# 6-line-matrix.net
KiCad netlist of a schematic drawn in EAGLE
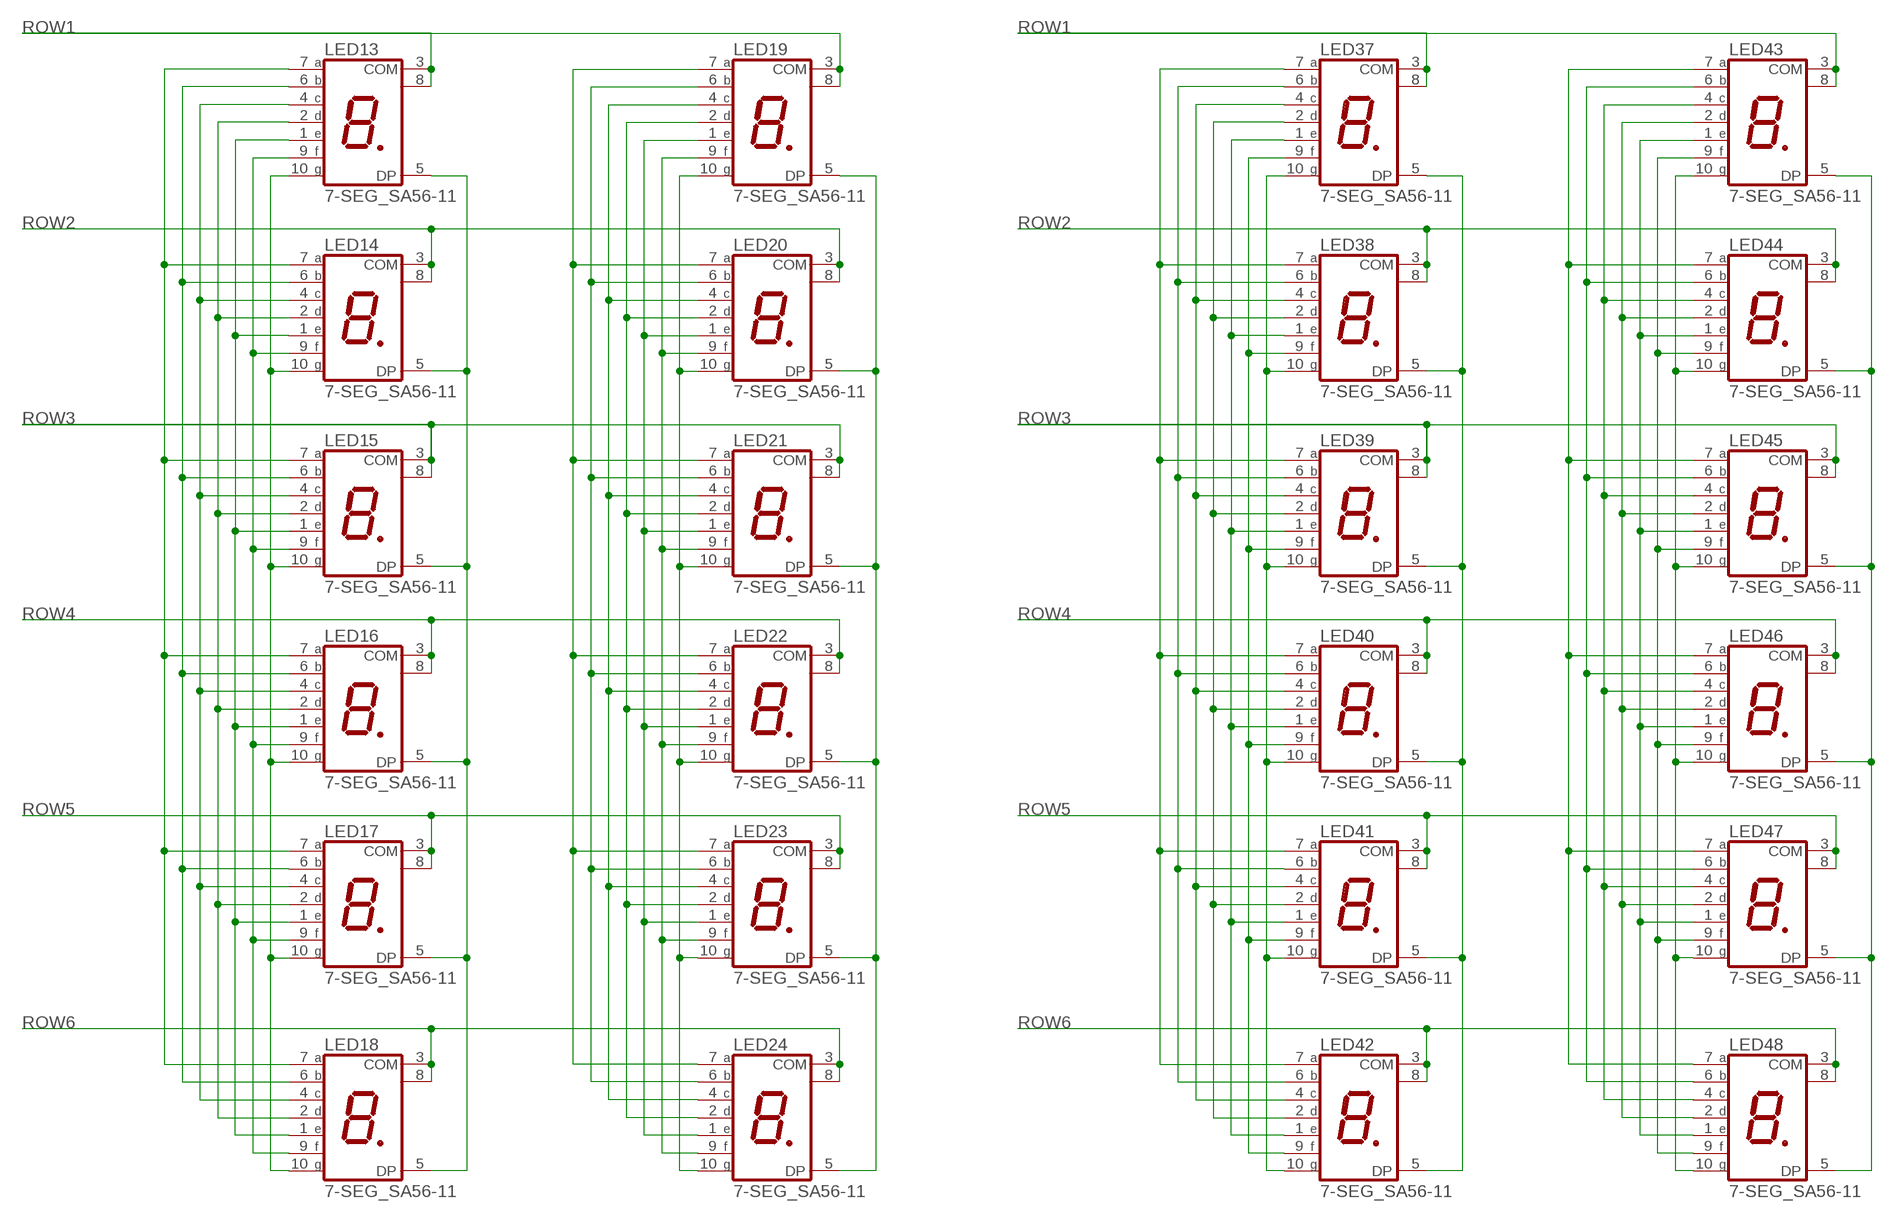
[diagram p0: schematic, sheet 1, part 1 of 2]
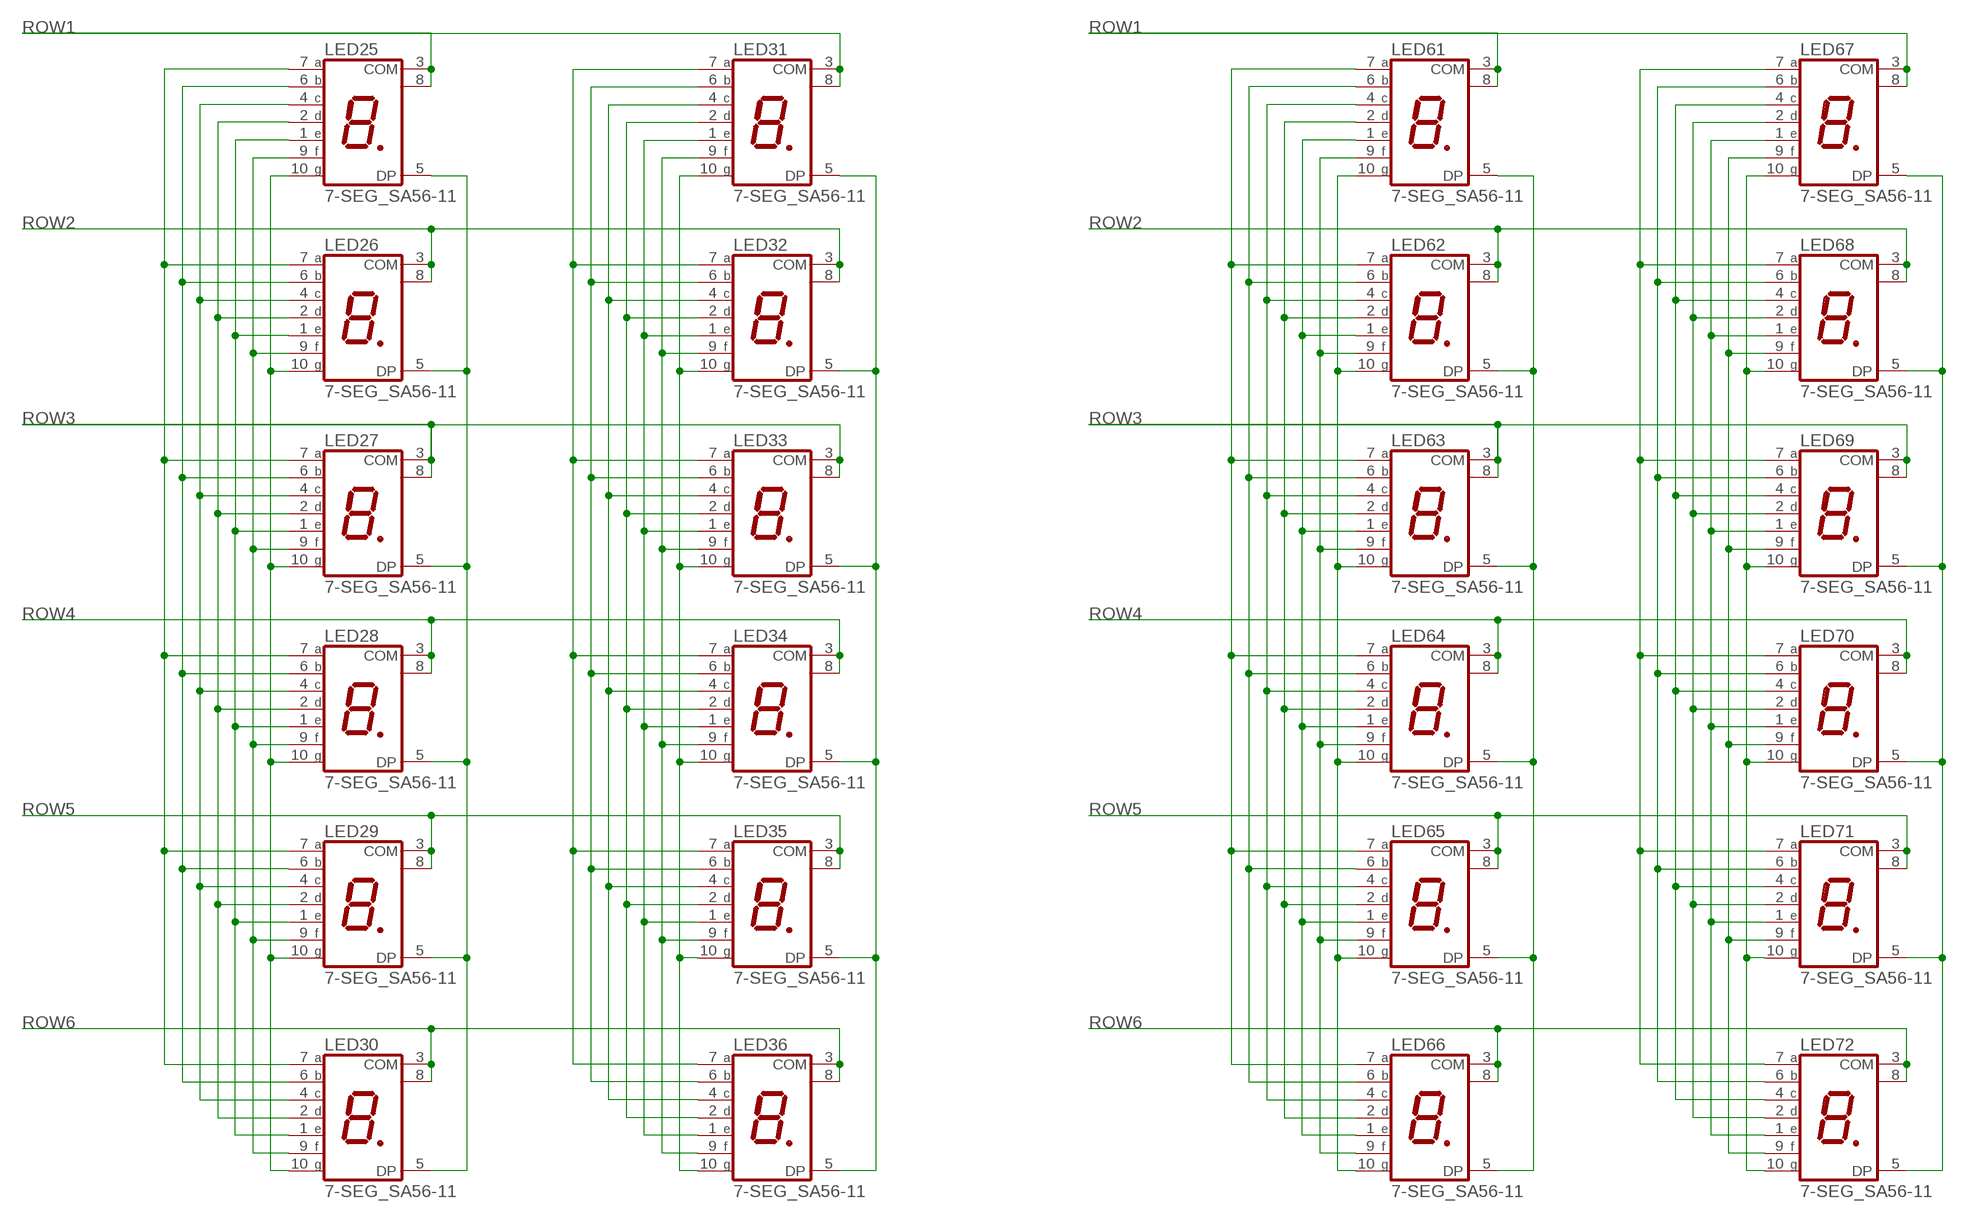
[diagram p1: schematic, sheet 1, part 2 of 2]

(export (version "E")
  (design (tool "Eeschema 10.0.6"))
  (components
    (comp (ref "LED13")
      (value "7-SEG_SA56-11")
      (footprint "eagle-import:SA56-11")
      (libsource (lib "eagle-import") (part "7-SEG_SA56-11"))
    )
    (comp (ref "LED14")
      (value "7-SEG_SA56-11")
      (footprint "eagle-import:SA56-11")
      (libsource (lib "eagle-import") (part "7-SEG_SA56-11"))
    )
    (comp (ref "LED15")
      (value "7-SEG_SA56-11")
      (footprint "eagle-import:SA56-11")
      (libsource (lib "eagle-import") (part "7-SEG_SA56-11"))
    )
    (comp (ref "LED16")
      (value "7-SEG_SA56-11")
      (footprint "eagle-import:SA56-11")
      (libsource (lib "eagle-import") (part "7-SEG_SA56-11"))
    )
    (comp (ref "LED17")
      (value "7-SEG_SA56-11")
      (footprint "eagle-import:SA56-11")
      (libsource (lib "eagle-import") (part "7-SEG_SA56-11"))
    )
    (comp (ref "LED18")
      (value "7-SEG_SA56-11")
      (footprint "eagle-import:SA56-11")
      (libsource (lib "eagle-import") (part "7-SEG_SA56-11"))
    )
    (comp (ref "LED19")
      (value "7-SEG_SA56-11")
      (footprint "eagle-import:SA56-11")
      (libsource (lib "eagle-import") (part "7-SEG_SA56-11"))
    )
    (comp (ref "LED20")
      (value "7-SEG_SA56-11")
      (footprint "eagle-import:SA56-11")
      (libsource (lib "eagle-import") (part "7-SEG_SA56-11"))
    )
    (comp (ref "LED21")
      (value "7-SEG_SA56-11")
      (footprint "eagle-import:SA56-11")
      (libsource (lib "eagle-import") (part "7-SEG_SA56-11"))
    )
    (comp (ref "LED22")
      (value "7-SEG_SA56-11")
      (footprint "eagle-import:SA56-11")
      (libsource (lib "eagle-import") (part "7-SEG_SA56-11"))
    )
    (comp (ref "LED23")
      (value "7-SEG_SA56-11")
      (footprint "eagle-import:SA56-11")
      (libsource (lib "eagle-import") (part "7-SEG_SA56-11"))
    )
    (comp (ref "LED24")
      (value "7-SEG_SA56-11")
      (footprint "eagle-import:SA56-11")
      (libsource (lib "eagle-import") (part "7-SEG_SA56-11"))
    )
    (comp (ref "LED25")
      (value "7-SEG_SA56-11")
      (footprint "eagle-import:SA56-11")
      (libsource (lib "eagle-import") (part "7-SEG_SA56-11"))
    )
    (comp (ref "LED26")
      (value "7-SEG_SA56-11")
      (footprint "eagle-import:SA56-11")
      (libsource (lib "eagle-import") (part "7-SEG_SA56-11"))
    )
    (comp (ref "LED27")
      (value "7-SEG_SA56-11")
      (footprint "eagle-import:SA56-11")
      (libsource (lib "eagle-import") (part "7-SEG_SA56-11"))
    )
    (comp (ref "LED28")
      (value "7-SEG_SA56-11")
      (footprint "eagle-import:SA56-11")
      (libsource (lib "eagle-import") (part "7-SEG_SA56-11"))
    )
    (comp (ref "LED29")
      (value "7-SEG_SA56-11")
      (footprint "eagle-import:SA56-11")
      (libsource (lib "eagle-import") (part "7-SEG_SA56-11"))
    )
    (comp (ref "LED30")
      (value "7-SEG_SA56-11")
      (footprint "eagle-import:SA56-11")
      (libsource (lib "eagle-import") (part "7-SEG_SA56-11"))
    )
    (comp (ref "LED31")
      (value "7-SEG_SA56-11")
      (footprint "eagle-import:SA56-11")
      (libsource (lib "eagle-import") (part "7-SEG_SA56-11"))
    )
    (comp (ref "LED32")
      (value "7-SEG_SA56-11")
      (footprint "eagle-import:SA56-11")
      (libsource (lib "eagle-import") (part "7-SEG_SA56-11"))
    )
    (comp (ref "LED33")
      (value "7-SEG_SA56-11")
      (footprint "eagle-import:SA56-11")
      (libsource (lib "eagle-import") (part "7-SEG_SA56-11"))
    )
    (comp (ref "LED34")
      (value "7-SEG_SA56-11")
      (footprint "eagle-import:SA56-11")
      (libsource (lib "eagle-import") (part "7-SEG_SA56-11"))
    )
    (comp (ref "LED35")
      (value "7-SEG_SA56-11")
      (footprint "eagle-import:SA56-11")
      (libsource (lib "eagle-import") (part "7-SEG_SA56-11"))
    )
    (comp (ref "LED36")
      (value "7-SEG_SA56-11")
      (footprint "eagle-import:SA56-11")
      (libsource (lib "eagle-import") (part "7-SEG_SA56-11"))
    )
    (comp (ref "LED37")
      (value "7-SEG_SA56-11")
      (footprint "eagle-import:SA56-11")
      (libsource (lib "eagle-import") (part "7-SEG_SA56-11"))
    )
    (comp (ref "LED38")
      (value "7-SEG_SA56-11")
      (footprint "eagle-import:SA56-11")
      (libsource (lib "eagle-import") (part "7-SEG_SA56-11"))
    )
    (comp (ref "LED39")
      (value "7-SEG_SA56-11")
      (footprint "eagle-import:SA56-11")
      (libsource (lib "eagle-import") (part "7-SEG_SA56-11"))
    )
    (comp (ref "LED40")
      (value "7-SEG_SA56-11")
      (footprint "eagle-import:SA56-11")
      (libsource (lib "eagle-import") (part "7-SEG_SA56-11"))
    )
    (comp (ref "LED41")
      (value "7-SEG_SA56-11")
      (footprint "eagle-import:SA56-11")
      (libsource (lib "eagle-import") (part "7-SEG_SA56-11"))
    )
    (comp (ref "LED42")
      (value "7-SEG_SA56-11")
      (footprint "eagle-import:SA56-11")
      (libsource (lib "eagle-import") (part "7-SEG_SA56-11"))
    )
    (comp (ref "LED43")
      (value "7-SEG_SA56-11")
      (footprint "eagle-import:SA56-11")
      (libsource (lib "eagle-import") (part "7-SEG_SA56-11"))
    )
    (comp (ref "LED44")
      (value "7-SEG_SA56-11")
      (footprint "eagle-import:SA56-11")
      (libsource (lib "eagle-import") (part "7-SEG_SA56-11"))
    )
    (comp (ref "LED45")
      (value "7-SEG_SA56-11")
      (footprint "eagle-import:SA56-11")
      (libsource (lib "eagle-import") (part "7-SEG_SA56-11"))
    )
    (comp (ref "LED46")
      (value "7-SEG_SA56-11")
      (footprint "eagle-import:SA56-11")
      (libsource (lib "eagle-import") (part "7-SEG_SA56-11"))
    )
    (comp (ref "LED47")
      (value "7-SEG_SA56-11")
      (footprint "eagle-import:SA56-11")
      (libsource (lib "eagle-import") (part "7-SEG_SA56-11"))
    )
    (comp (ref "LED48")
      (value "7-SEG_SA56-11")
      (footprint "eagle-import:SA56-11")
      (libsource (lib "eagle-import") (part "7-SEG_SA56-11"))
    )
    (comp (ref "LED61")
      (value "7-SEG_SA56-11")
      (footprint "eagle-import:SA56-11")
      (libsource (lib "eagle-import") (part "7-SEG_SA56-11"))
    )
    (comp (ref "LED62")
      (value "7-SEG_SA56-11")
      (footprint "eagle-import:SA56-11")
      (libsource (lib "eagle-import") (part "7-SEG_SA56-11"))
    )
    (comp (ref "LED63")
      (value "7-SEG_SA56-11")
      (footprint "eagle-import:SA56-11")
      (libsource (lib "eagle-import") (part "7-SEG_SA56-11"))
    )
    (comp (ref "LED64")
      (value "7-SEG_SA56-11")
      (footprint "eagle-import:SA56-11")
      (libsource (lib "eagle-import") (part "7-SEG_SA56-11"))
    )
    (comp (ref "LED65")
      (value "7-SEG_SA56-11")
      (footprint "eagle-import:SA56-11")
      (libsource (lib "eagle-import") (part "7-SEG_SA56-11"))
    )
    (comp (ref "LED66")
      (value "7-SEG_SA56-11")
      (footprint "eagle-import:SA56-11")
      (libsource (lib "eagle-import") (part "7-SEG_SA56-11"))
    )
    (comp (ref "LED67")
      (value "7-SEG_SA56-11")
      (footprint "eagle-import:SA56-11")
      (libsource (lib "eagle-import") (part "7-SEG_SA56-11"))
    )
    (comp (ref "LED68")
      (value "7-SEG_SA56-11")
      (footprint "eagle-import:SA56-11")
      (libsource (lib "eagle-import") (part "7-SEG_SA56-11"))
    )
    (comp (ref "LED69")
      (value "7-SEG_SA56-11")
      (footprint "eagle-import:SA56-11")
      (libsource (lib "eagle-import") (part "7-SEG_SA56-11"))
    )
    (comp (ref "LED70")
      (value "7-SEG_SA56-11")
      (footprint "eagle-import:SA56-11")
      (libsource (lib "eagle-import") (part "7-SEG_SA56-11"))
    )
    (comp (ref "LED71")
      (value "7-SEG_SA56-11")
      (footprint "eagle-import:SA56-11")
      (libsource (lib "eagle-import") (part "7-SEG_SA56-11"))
    )
    (comp (ref "LED72")
      (value "7-SEG_SA56-11")
      (footprint "eagle-import:SA56-11")
      (libsource (lib "eagle-import") (part "7-SEG_SA56-11"))
    )
  )
  (nets
    (net (code "1") (name "/ROW1") (class "Default")
      (node (ref "LED13") (pin "3") (pinfunction "COM_3") (pintype "passive"))
      (node (ref "LED13") (pin "8") (pinfunction "COM_8") (pintype "passive"))
      (node (ref "LED19") (pin "3") (pinfunction "COM_3") (pintype "passive"))
      (node (ref "LED19") (pin "8") (pinfunction "COM_8") (pintype "passive"))
      (node (ref "LED25") (pin "3") (pinfunction "COM_3") (pintype "passive"))
      (node (ref "LED25") (pin "8") (pinfunction "COM_8") (pintype "passive"))
      (node (ref "LED31") (pin "3") (pinfunction "COM_3") (pintype "passive"))
      (node (ref "LED31") (pin "8") (pinfunction "COM_8") (pintype "passive"))
      (node (ref "LED37") (pin "3") (pinfunction "COM_3") (pintype "passive"))
      (node (ref "LED37") (pin "8") (pinfunction "COM_8") (pintype "passive"))
      (node (ref "LED43") (pin "3") (pinfunction "COM_3") (pintype "passive"))
      (node (ref "LED43") (pin "8") (pinfunction "COM_8") (pintype "passive"))
      (node (ref "LED61") (pin "3") (pinfunction "COM_3") (pintype "passive"))
      (node (ref "LED61") (pin "8") (pinfunction "COM_8") (pintype "passive"))
      (node (ref "LED67") (pin "3") (pinfunction "COM_3") (pintype "passive"))
      (node (ref "LED67") (pin "8") (pinfunction "COM_8") (pintype "passive"))
    )
    (net (code "2") (name "/ROW2") (class "Default")
      (node (ref "LED14") (pin "3") (pinfunction "COM_3") (pintype "passive"))
      (node (ref "LED14") (pin "8") (pinfunction "COM_8") (pintype "passive"))
      (node (ref "LED20") (pin "3") (pinfunction "COM_3") (pintype "passive"))
      (node (ref "LED20") (pin "8") (pinfunction "COM_8") (pintype "passive"))
      (node (ref "LED26") (pin "3") (pinfunction "COM_3") (pintype "passive"))
      (node (ref "LED26") (pin "8") (pinfunction "COM_8") (pintype "passive"))
      (node (ref "LED32") (pin "3") (pinfunction "COM_3") (pintype "passive"))
      (node (ref "LED32") (pin "8") (pinfunction "COM_8") (pintype "passive"))
      (node (ref "LED38") (pin "3") (pinfunction "COM_3") (pintype "passive"))
      (node (ref "LED38") (pin "8") (pinfunction "COM_8") (pintype "passive"))
      (node (ref "LED44") (pin "3") (pinfunction "COM_3") (pintype "passive"))
      (node (ref "LED44") (pin "8") (pinfunction "COM_8") (pintype "passive"))
      (node (ref "LED62") (pin "3") (pinfunction "COM_3") (pintype "passive"))
      (node (ref "LED62") (pin "8") (pinfunction "COM_8") (pintype "passive"))
      (node (ref "LED68") (pin "3") (pinfunction "COM_3") (pintype "passive"))
      (node (ref "LED68") (pin "8") (pinfunction "COM_8") (pintype "passive"))
    )
    (net (code "3") (name "/ROW3") (class "Default")
      (node (ref "LED15") (pin "3") (pinfunction "COM_3") (pintype "passive"))
      (node (ref "LED15") (pin "8") (pinfunction "COM_8") (pintype "passive"))
      (node (ref "LED21") (pin "3") (pinfunction "COM_3") (pintype "passive"))
      (node (ref "LED21") (pin "8") (pinfunction "COM_8") (pintype "passive"))
      (node (ref "LED27") (pin "3") (pinfunction "COM_3") (pintype "passive"))
      (node (ref "LED27") (pin "8") (pinfunction "COM_8") (pintype "passive"))
      (node (ref "LED33") (pin "3") (pinfunction "COM_3") (pintype "passive"))
      (node (ref "LED33") (pin "8") (pinfunction "COM_8") (pintype "passive"))
      (node (ref "LED39") (pin "3") (pinfunction "COM_3") (pintype "passive"))
      (node (ref "LED39") (pin "8") (pinfunction "COM_8") (pintype "passive"))
      (node (ref "LED45") (pin "3") (pinfunction "COM_3") (pintype "passive"))
      (node (ref "LED45") (pin "8") (pinfunction "COM_8") (pintype "passive"))
      (node (ref "LED63") (pin "3") (pinfunction "COM_3") (pintype "passive"))
      (node (ref "LED63") (pin "8") (pinfunction "COM_8") (pintype "passive"))
      (node (ref "LED69") (pin "3") (pinfunction "COM_3") (pintype "passive"))
      (node (ref "LED69") (pin "8") (pinfunction "COM_8") (pintype "passive"))
    )
    (net (code "4") (name "/ROW4") (class "Default")
      (node (ref "LED16") (pin "3") (pinfunction "COM_3") (pintype "passive"))
      (node (ref "LED16") (pin "8") (pinfunction "COM_8") (pintype "passive"))
      (node (ref "LED22") (pin "3") (pinfunction "COM_3") (pintype "passive"))
      (node (ref "LED22") (pin "8") (pinfunction "COM_8") (pintype "passive"))
      (node (ref "LED28") (pin "3") (pinfunction "COM_3") (pintype "passive"))
      (node (ref "LED28") (pin "8") (pinfunction "COM_8") (pintype "passive"))
      (node (ref "LED34") (pin "3") (pinfunction "COM_3") (pintype "passive"))
      (node (ref "LED34") (pin "8") (pinfunction "COM_8") (pintype "passive"))
      (node (ref "LED40") (pin "3") (pinfunction "COM_3") (pintype "passive"))
      (node (ref "LED40") (pin "8") (pinfunction "COM_8") (pintype "passive"))
      (node (ref "LED46") (pin "3") (pinfunction "COM_3") (pintype "passive"))
      (node (ref "LED46") (pin "8") (pinfunction "COM_8") (pintype "passive"))
      (node (ref "LED64") (pin "3") (pinfunction "COM_3") (pintype "passive"))
      (node (ref "LED64") (pin "8") (pinfunction "COM_8") (pintype "passive"))
      (node (ref "LED70") (pin "3") (pinfunction "COM_3") (pintype "passive"))
      (node (ref "LED70") (pin "8") (pinfunction "COM_8") (pintype "passive"))
    )
    (net (code "5") (name "/ROW5") (class "Default")
      (node (ref "LED17") (pin "3") (pinfunction "COM_3") (pintype "passive"))
      (node (ref "LED17") (pin "8") (pinfunction "COM_8") (pintype "passive"))
      (node (ref "LED23") (pin "3") (pinfunction "COM_3") (pintype "passive"))
      (node (ref "LED23") (pin "8") (pinfunction "COM_8") (pintype "passive"))
      (node (ref "LED29") (pin "3") (pinfunction "COM_3") (pintype "passive"))
      (node (ref "LED29") (pin "8") (pinfunction "COM_8") (pintype "passive"))
      (node (ref "LED35") (pin "3") (pinfunction "COM_3") (pintype "passive"))
      (node (ref "LED35") (pin "8") (pinfunction "COM_8") (pintype "passive"))
      (node (ref "LED41") (pin "3") (pinfunction "COM_3") (pintype "passive"))
      (node (ref "LED41") (pin "8") (pinfunction "COM_8") (pintype "passive"))
      (node (ref "LED47") (pin "3") (pinfunction "COM_3") (pintype "passive"))
      (node (ref "LED47") (pin "8") (pinfunction "COM_8") (pintype "passive"))
      (node (ref "LED65") (pin "3") (pinfunction "COM_3") (pintype "passive"))
      (node (ref "LED65") (pin "8") (pinfunction "COM_8") (pintype "passive"))
      (node (ref "LED71") (pin "3") (pinfunction "COM_3") (pintype "passive"))
      (node (ref "LED71") (pin "8") (pinfunction "COM_8") (pintype "passive"))
    )
    (net (code "6") (name "/ROW6") (class "Default")
      (node (ref "LED18") (pin "3") (pinfunction "COM_3") (pintype "passive"))
      (node (ref "LED18") (pin "8") (pinfunction "COM_8") (pintype "passive"))
      (node (ref "LED24") (pin "3") (pinfunction "COM_3") (pintype "passive"))
      (node (ref "LED24") (pin "8") (pinfunction "COM_8") (pintype "passive"))
      (node (ref "LED30") (pin "3") (pinfunction "COM_3") (pintype "passive"))
      (node (ref "LED30") (pin "8") (pinfunction "COM_8") (pintype "passive"))
      (node (ref "LED36") (pin "3") (pinfunction "COM_3") (pintype "passive"))
      (node (ref "LED36") (pin "8") (pinfunction "COM_8") (pintype "passive"))
      (node (ref "LED42") (pin "3") (pinfunction "COM_3") (pintype "passive"))
      (node (ref "LED42") (pin "8") (pinfunction "COM_8") (pintype "passive"))
      (node (ref "LED48") (pin "3") (pinfunction "COM_3") (pintype "passive"))
      (node (ref "LED48") (pin "8") (pinfunction "COM_8") (pintype "passive"))
      (node (ref "LED66") (pin "3") (pinfunction "COM_3") (pintype "passive"))
      (node (ref "LED66") (pin "8") (pinfunction "COM_8") (pintype "passive"))
      (node (ref "LED72") (pin "3") (pinfunction "COM_3") (pintype "passive"))
      (node (ref "LED72") (pin "8") (pinfunction "COM_8") (pintype "passive"))
    )
    (net (code "7") (name "Net-(LED13-A)") (class "Default")
      (node (ref "LED13") (pin "7") (pinfunction "A_7") (pintype "passive"))
      (node (ref "LED14") (pin "7") (pinfunction "A_7") (pintype "passive"))
      (node (ref "LED15") (pin "7") (pinfunction "A_7") (pintype "passive"))
      (node (ref "LED16") (pin "7") (pinfunction "A_7") (pintype "passive"))
      (node (ref "LED17") (pin "7") (pinfunction "A_7") (pintype "passive"))
      (node (ref "LED18") (pin "7") (pinfunction "A_7") (pintype "passive"))
    )
    (net (code "8") (name "Net-(LED13-B)") (class "Default")
      (node (ref "LED13") (pin "6") (pinfunction "B_6") (pintype "passive"))
      (node (ref "LED14") (pin "6") (pinfunction "B_6") (pintype "passive"))
      (node (ref "LED15") (pin "6") (pinfunction "B_6") (pintype "passive"))
      (node (ref "LED16") (pin "6") (pinfunction "B_6") (pintype "passive"))
      (node (ref "LED17") (pin "6") (pinfunction "B_6") (pintype "passive"))
      (node (ref "LED18") (pin "6") (pinfunction "B_6") (pintype "passive"))
    )
    (net (code "9") (name "Net-(LED13-C)") (class "Default")
      (node (ref "LED13") (pin "4") (pinfunction "C_4") (pintype "passive"))
      (node (ref "LED14") (pin "4") (pinfunction "C_4") (pintype "passive"))
      (node (ref "LED15") (pin "4") (pinfunction "C_4") (pintype "passive"))
      (node (ref "LED16") (pin "4") (pinfunction "C_4") (pintype "passive"))
      (node (ref "LED17") (pin "4") (pinfunction "C_4") (pintype "passive"))
      (node (ref "LED18") (pin "4") (pinfunction "C_4") (pintype "passive"))
    )
    (net (code "10") (name "Net-(LED13-D)") (class "Default")
      (node (ref "LED13") (pin "2") (pinfunction "D_2") (pintype "passive"))
      (node (ref "LED14") (pin "2") (pinfunction "D_2") (pintype "passive"))
      (node (ref "LED15") (pin "2") (pinfunction "D_2") (pintype "passive"))
      (node (ref "LED16") (pin "2") (pinfunction "D_2") (pintype "passive"))
      (node (ref "LED17") (pin "2") (pinfunction "D_2") (pintype "passive"))
      (node (ref "LED18") (pin "2") (pinfunction "D_2") (pintype "passive"))
    )
    (net (code "11") (name "Net-(LED13-DP)") (class "Default")
      (node (ref "LED13") (pin "5") (pinfunction "DP_5") (pintype "passive"))
      (node (ref "LED14") (pin "5") (pinfunction "DP_5") (pintype "passive"))
      (node (ref "LED15") (pin "5") (pinfunction "DP_5") (pintype "passive"))
      (node (ref "LED16") (pin "5") (pinfunction "DP_5") (pintype "passive"))
      (node (ref "LED17") (pin "5") (pinfunction "DP_5") (pintype "passive"))
      (node (ref "LED18") (pin "5") (pinfunction "DP_5") (pintype "passive"))
    )
    (net (code "12") (name "Net-(LED13-E)") (class "Default")
      (node (ref "LED13") (pin "1") (pinfunction "E_1") (pintype "passive"))
      (node (ref "LED14") (pin "1") (pinfunction "E_1") (pintype "passive"))
      (node (ref "LED15") (pin "1") (pinfunction "E_1") (pintype "passive"))
      (node (ref "LED16") (pin "1") (pinfunction "E_1") (pintype "passive"))
      (node (ref "LED17") (pin "1") (pinfunction "E_1") (pintype "passive"))
      (node (ref "LED18") (pin "1") (pinfunction "E_1") (pintype "passive"))
    )
    (net (code "13") (name "Net-(LED13-F)") (class "Default")
      (node (ref "LED13") (pin "9") (pinfunction "F_9") (pintype "passive"))
      (node (ref "LED14") (pin "9") (pinfunction "F_9") (pintype "passive"))
      (node (ref "LED15") (pin "9") (pinfunction "F_9") (pintype "passive"))
      (node (ref "LED16") (pin "9") (pinfunction "F_9") (pintype "passive"))
      (node (ref "LED17") (pin "9") (pinfunction "F_9") (pintype "passive"))
      (node (ref "LED18") (pin "9") (pinfunction "F_9") (pintype "passive"))
    )
    (net (code "14") (name "Net-(LED13-G)") (class "Default")
      (node (ref "LED13") (pin "10") (pinfunction "G_10") (pintype "passive"))
      (node (ref "LED14") (pin "10") (pinfunction "G_10") (pintype "passive"))
      (node (ref "LED15") (pin "10") (pinfunction "G_10") (pintype "passive"))
      (node (ref "LED16") (pin "10") (pinfunction "G_10") (pintype "passive"))
      (node (ref "LED17") (pin "10") (pinfunction "G_10") (pintype "passive"))
      (node (ref "LED18") (pin "10") (pinfunction "G_10") (pintype "passive"))
    )
    (net (code "15") (name "Net-(LED19-A)") (class "Default")
      (node (ref "LED19") (pin "7") (pinfunction "A_7") (pintype "passive"))
      (node (ref "LED20") (pin "7") (pinfunction "A_7") (pintype "passive"))
      (node (ref "LED21") (pin "7") (pinfunction "A_7") (pintype "passive"))
      (node (ref "LED22") (pin "7") (pinfunction "A_7") (pintype "passive"))
      (node (ref "LED23") (pin "7") (pinfunction "A_7") (pintype "passive"))
      (node (ref "LED24") (pin "7") (pinfunction "A_7") (pintype "passive"))
    )
    (net (code "16") (name "Net-(LED19-B)") (class "Default")
      (node (ref "LED19") (pin "6") (pinfunction "B_6") (pintype "passive"))
      (node (ref "LED20") (pin "6") (pinfunction "B_6") (pintype "passive"))
      (node (ref "LED21") (pin "6") (pinfunction "B_6") (pintype "passive"))
      (node (ref "LED22") (pin "6") (pinfunction "B_6") (pintype "passive"))
      (node (ref "LED23") (pin "6") (pinfunction "B_6") (pintype "passive"))
      (node (ref "LED24") (pin "6") (pinfunction "B_6") (pintype "passive"))
    )
    (net (code "17") (name "Net-(LED19-C)") (class "Default")
      (node (ref "LED19") (pin "4") (pinfunction "C_4") (pintype "passive"))
      (node (ref "LED20") (pin "4") (pinfunction "C_4") (pintype "passive"))
      (node (ref "LED21") (pin "4") (pinfunction "C_4") (pintype "passive"))
      (node (ref "LED22") (pin "4") (pinfunction "C_4") (pintype "passive"))
      (node (ref "LED23") (pin "4") (pinfunction "C_4") (pintype "passive"))
      (node (ref "LED24") (pin "4") (pinfunction "C_4") (pintype "passive"))
    )
    (net (code "18") (name "Net-(LED19-D)") (class "Default")
      (node (ref "LED19") (pin "2") (pinfunction "D_2") (pintype "passive"))
      (node (ref "LED20") (pin "2") (pinfunction "D_2") (pintype "passive"))
      (node (ref "LED21") (pin "2") (pinfunction "D_2") (pintype "passive"))
      (node (ref "LED22") (pin "2") (pinfunction "D_2") (pintype "passive"))
      (node (ref "LED23") (pin "2") (pinfunction "D_2") (pintype "passive"))
      (node (ref "LED24") (pin "2") (pinfunction "D_2") (pintype "passive"))
    )
    (net (code "19") (name "Net-(LED19-DP)") (class "Default")
      (node (ref "LED19") (pin "5") (pinfunction "DP_5") (pintype "passive"))
      (node (ref "LED20") (pin "5") (pinfunction "DP_5") (pintype "passive"))
      (node (ref "LED21") (pin "5") (pinfunction "DP_5") (pintype "passive"))
      (node (ref "LED22") (pin "5") (pinfunction "DP_5") (pintype "passive"))
      (node (ref "LED23") (pin "5") (pinfunction "DP_5") (pintype "passive"))
      (node (ref "LED24") (pin "5") (pinfunction "DP_5") (pintype "passive"))
    )
    (net (code "20") (name "Net-(LED19-E)") (class "Default")
      (node (ref "LED19") (pin "1") (pinfunction "E_1") (pintype "passive"))
      (node (ref "LED20") (pin "1") (pinfunction "E_1") (pintype "passive"))
      (node (ref "LED21") (pin "1") (pinfunction "E_1") (pintype "passive"))
      (node (ref "LED22") (pin "1") (pinfunction "E_1") (pintype "passive"))
      (node (ref "LED23") (pin "1") (pinfunction "E_1") (pintype "passive"))
      (node (ref "LED24") (pin "1") (pinfunction "E_1") (pintype "passive"))
    )
    (net (code "21") (name "Net-(LED19-F)") (class "Default")
      (node (ref "LED19") (pin "9") (pinfunction "F_9") (pintype "passive"))
      (node (ref "LED20") (pin "9") (pinfunction "F_9") (pintype "passive"))
      (node (ref "LED21") (pin "9") (pinfunction "F_9") (pintype "passive"))
      (node (ref "LED22") (pin "9") (pinfunction "F_9") (pintype "passive"))
      (node (ref "LED23") (pin "9") (pinfunction "F_9") (pintype "passive"))
      (node (ref "LED24") (pin "9") (pinfunction "F_9") (pintype "passive"))
    )
    (net (code "22") (name "Net-(LED19-G)") (class "Default")
      (node (ref "LED19") (pin "10") (pinfunction "G_10") (pintype "passive"))
      (node (ref "LED20") (pin "10") (pinfunction "G_10") (pintype "passive"))
      (node (ref "LED21") (pin "10") (pinfunction "G_10") (pintype "passive"))
      (node (ref "LED22") (pin "10") (pinfunction "G_10") (pintype "passive"))
      (node (ref "LED23") (pin "10") (pinfunction "G_10") (pintype "passive"))
      (node (ref "LED24") (pin "10") (pinfunction "G_10") (pintype "passive"))
    )
    (net (code "23") (name "Net-(LED25-A)") (class "Default")
      (node (ref "LED25") (pin "7") (pinfunction "A_7") (pintype "passive"))
      (node (ref "LED26") (pin "7") (pinfunction "A_7") (pintype "passive"))
      (node (ref "LED27") (pin "7") (pinfunction "A_7") (pintype "passive"))
      (node (ref "LED28") (pin "7") (pinfunction "A_7") (pintype "passive"))
      (node (ref "LED29") (pin "7") (pinfunction "A_7") (pintype "passive"))
      (node (ref "LED30") (pin "7") (pinfunction "A_7") (pintype "passive"))
    )
    (net (code "24") (name "Net-(LED25-B)") (class "Default")
      (node (ref "LED25") (pin "6") (pinfunction "B_6") (pintype "passive"))
      (node (ref "LED26") (pin "6") (pinfunction "B_6") (pintype "passive"))
      (node (ref "LED27") (pin "6") (pinfunction "B_6") (pintype "passive"))
      (node (ref "LED28") (pin "6") (pinfunction "B_6") (pintype "passive"))
      (node (ref "LED29") (pin "6") (pinfunction "B_6") (pintype "passive"))
      (node (ref "LED30") (pin "6") (pinfunction "B_6") (pintype "passive"))
    )
    (net (code "25") (name "Net-(LED25-C)") (class "Default")
      (node (ref "LED25") (pin "4") (pinfunction "C_4") (pintype "passive"))
      (node (ref "LED26") (pin "4") (pinfunction "C_4") (pintype "passive"))
      (node (ref "LED27") (pin "4") (pinfunction "C_4") (pintype "passive"))
      (node (ref "LED28") (pin "4") (pinfunction "C_4") (pintype "passive"))
      (node (ref "LED29") (pin "4") (pinfunction "C_4") (pintype "passive"))
      (node (ref "LED30") (pin "4") (pinfunction "C_4") (pintype "passive"))
    )
    (net (code "26") (name "Net-(LED25-D)") (class "Default")
      (node (ref "LED25") (pin "2") (pinfunction "D_2") (pintype "passive"))
      (node (ref "LED26") (pin "2") (pinfunction "D_2") (pintype "passive"))
      (node (ref "LED27") (pin "2") (pinfunction "D_2") (pintype "passive"))
      (node (ref "LED28") (pin "2") (pinfunction "D_2") (pintype "passive"))
      (node (ref "LED29") (pin "2") (pinfunction "D_2") (pintype "passive"))
      (node (ref "LED30") (pin "2") (pinfunction "D_2") (pintype "passive"))
    )
    (net (code "27") (name "Net-(LED25-DP)") (class "Default")
      (node (ref "LED25") (pin "5") (pinfunction "DP_5") (pintype "passive"))
      (node (ref "LED26") (pin "5") (pinfunction "DP_5") (pintype "passive"))
      (node (ref "LED27") (pin "5") (pinfunction "DP_5") (pintype "passive"))
      (node (ref "LED28") (pin "5") (pinfunction "DP_5") (pintype "passive"))
      (node (ref "LED29") (pin "5") (pinfunction "DP_5") (pintype "passive"))
      (node (ref "LED30") (pin "5") (pinfunction "DP_5") (pintype "passive"))
    )
    (net (code "28") (name "Net-(LED25-E)") (class "Default")
      (node (ref "LED25") (pin "1") (pinfunction "E_1") (pintype "passive"))
      (node (ref "LED26") (pin "1") (pinfunction "E_1") (pintype "passive"))
      (node (ref "LED27") (pin "1") (pinfunction "E_1") (pintype "passive"))
      (node (ref "LED28") (pin "1") (pinfunction "E_1") (pintype "passive"))
      (node (ref "LED29") (pin "1") (pinfunction "E_1") (pintype "passive"))
      (node (ref "LED30") (pin "1") (pinfunction "E_1") (pintype "passive"))
    )
    (net (code "29") (name "Net-(LED25-F)") (class "Default")
      (node (ref "LED25") (pin "9") (pinfunction "F_9") (pintype "passive"))
      (node (ref "LED26") (pin "9") (pinfunction "F_9") (pintype "passive"))
      (node (ref "LED27") (pin "9") (pinfunction "F_9") (pintype "passive"))
      (node (ref "LED28") (pin "9") (pinfunction "F_9") (pintype "passive"))
      (node (ref "LED29") (pin "9") (pinfunction "F_9") (pintype "passive"))
      (node (ref "LED30") (pin "9") (pinfunction "F_9") (pintype "passive"))
    )
    (net (code "30") (name "Net-(LED25-G)") (class "Default")
      (node (ref "LED25") (pin "10") (pinfunction "G_10") (pintype "passive"))
      (node (ref "LED26") (pin "10") (pinfunction "G_10") (pintype "passive"))
      (node (ref "LED27") (pin "10") (pinfunction "G_10") (pintype "passive"))
      (node (ref "LED28") (pin "10") (pinfunction "G_10") (pintype "passive"))
      (node (ref "LED29") (pin "10") (pinfunction "G_10") (pintype "passive"))
      (node (ref "LED30") (pin "10") (pinfunction "G_10") (pintype "passive"))
    )
    (net (code "31") (name "Net-(LED31-A)") (class "Default")
      (node (ref "LED31") (pin "7") (pinfunction "A_7") (pintype "passive"))
      (node (ref "LED32") (pin "7") (pinfunction "A_7") (pintype "passive"))
      (node (ref "LED33") (pin "7") (pinfunction "A_7") (pintype "passive"))
      (node (ref "LED34") (pin "7") (pinfunction "A_7") (pintype "passive"))
      (node (ref "LED35") (pin "7") (pinfunction "A_7") (pintype "passive"))
      (node (ref "LED36") (pin "7") (pinfunction "A_7") (pintype "passive"))
    )
    (net (code "32") (name "Net-(LED31-B)") (class "Default")
      (node (ref "LED31") (pin "6") (pinfunction "B_6") (pintype "passive"))
      (node (ref "LED32") (pin "6") (pinfunction "B_6") (pintype "passive"))
      (node (ref "LED33") (pin "6") (pinfunction "B_6") (pintype "passive"))
      (node (ref "LED34") (pin "6") (pinfunction "B_6") (pintype "passive"))
      (node (ref "LED35") (pin "6") (pinfunction "B_6") (pintype "passive"))
      (node (ref "LED36") (pin "6") (pinfunction "B_6") (pintype "passive"))
    )
    (net (code "33") (name "Net-(LED31-C)") (class "Default")
      (node (ref "LED31") (pin "4") (pinfunction "C_4") (pintype "passive"))
      (node (ref "LED32") (pin "4") (pinfunction "C_4") (pintype "passive"))
      (node (ref "LED33") (pin "4") (pinfunction "C_4") (pintype "passive"))
      (node (ref "LED34") (pin "4") (pinfunction "C_4") (pintype "passive"))
      (node (ref "LED35") (pin "4") (pinfunction "C_4") (pintype "passive"))
      (node (ref "LED36") (pin "4") (pinfunction "C_4") (pintype "passive"))
    )
    (net (code "34") (name "Net-(LED31-D)") (class "Default")
      (node (ref "LED31") (pin "2") (pinfunction "D_2") (pintype "passive"))
      (node (ref "LED32") (pin "2") (pinfunction "D_2") (pintype "passive"))
      (node (ref "LED33") (pin "2") (pinfunction "D_2") (pintype "passive"))
      (node (ref "LED34") (pin "2") (pinfunction "D_2") (pintype "passive"))
      (node (ref "LED35") (pin "2") (pinfunction "D_2") (pintype "passive"))
      (node (ref "LED36") (pin "2") (pinfunction "D_2") (pintype "passive"))
    )
    (net (code "35") (name "Net-(LED31-DP)") (class "Default")
      (node (ref "LED31") (pin "5") (pinfunction "DP_5") (pintype "passive"))
      (node (ref "LED32") (pin "5") (pinfunction "DP_5") (pintype "passive"))
      (node (ref "LED33") (pin "5") (pinfunction "DP_5") (pintype "passive"))
      (node (ref "LED34") (pin "5") (pinfunction "DP_5") (pintype "passive"))
      (node (ref "LED35") (pin "5") (pinfunction "DP_5") (pintype "passive"))
      (node (ref "LED36") (pin "5") (pinfunction "DP_5") (pintype "passive"))
    )
    (net (code "36") (name "Net-(LED31-E)") (class "Default")
      (node (ref "LED31") (pin "1") (pinfunction "E_1") (pintype "passive"))
      (node (ref "LED32") (pin "1") (pinfunction "E_1") (pintype "passive"))
      (node (ref "LED33") (pin "1") (pinfunction "E_1") (pintype "passive"))
      (node (ref "LED34") (pin "1") (pinfunction "E_1") (pintype "passive"))
      (node (ref "LED35") (pin "1") (pinfunction "E_1") (pintype "passive"))
      (node (ref "LED36") (pin "1") (pinfunction "E_1") (pintype "passive"))
    )
    (net (code "37") (name "Net-(LED31-F)") (class "Default")
      (node (ref "LED31") (pin "9") (pinfunction "F_9") (pintype "passive"))
      (node (ref "LED32") (pin "9") (pinfunction "F_9") (pintype "passive"))
      (node (ref "LED33") (pin "9") (pinfunction "F_9") (pintype "passive"))
      (node (ref "LED34") (pin "9") (pinfunction "F_9") (pintype "passive"))
      (node (ref "LED35") (pin "9") (pinfunction "F_9") (pintype "passive"))
      (node (ref "LED36") (pin "9") (pinfunction "F_9") (pintype "passive"))
    )
    (net (code "38") (name "Net-(LED31-G)") (class "Default")
      (node (ref "LED31") (pin "10") (pinfunction "G_10") (pintype "passive"))
      (node (ref "LED32") (pin "10") (pinfunction "G_10") (pintype "passive"))
      (node (ref "LED33") (pin "10") (pinfunction "G_10") (pintype "passive"))
      (node (ref "LED34") (pin "10") (pinfunction "G_10") (pintype "passive"))
      (node (ref "LED35") (pin "10") (pinfunction "G_10") (pintype "passive"))
      (node (ref "LED36") (pin "10") (pinfunction "G_10") (pintype "passive"))
    )
    (net (code "39") (name "Net-(LED37-A)") (class "Default")
      (node (ref "LED37") (pin "7") (pinfunction "A_7") (pintype "passive"))
      (node (ref "LED38") (pin "7") (pinfunction "A_7") (pintype "passive"))
      (node (ref "LED39") (pin "7") (pinfunction "A_7") (pintype "passive"))
      (node (ref "LED40") (pin "7") (pinfunction "A_7") (pintype "passive"))
      (node (ref "LED41") (pin "7") (pinfunction "A_7") (pintype "passive"))
      (node (ref "LED42") (pin "7") (pinfunction "A_7") (pintype "passive"))
    )
    (net (code "40") (name "Net-(LED37-B)") (class "Default")
      (node (ref "LED37") (pin "6") (pinfunction "B_6") (pintype "passive"))
      (node (ref "LED38") (pin "6") (pinfunction "B_6") (pintype "passive"))
      (node (ref "LED39") (pin "6") (pinfunction "B_6") (pintype "passive"))
      (node (ref "LED40") (pin "6") (pinfunction "B_6") (pintype "passive"))
      (node (ref "LED41") (pin "6") (pinfunction "B_6") (pintype "passive"))
      (node (ref "LED42") (pin "6") (pinfunction "B_6") (pintype "passive"))
    )
    (net (code "41") (name "Net-(LED37-C)") (class "Default")
      (node (ref "LED37") (pin "4") (pinfunction "C_4") (pintype "passive"))
      (node (ref "LED38") (pin "4") (pinfunction "C_4") (pintype "passive"))
      (node (ref "LED39") (pin "4") (pinfunction "C_4") (pintype "passive"))
      (node (ref "LED40") (pin "4") (pinfunction "C_4") (pintype "passive"))
      (node (ref "LED41") (pin "4") (pinfunction "C_4") (pintype "passive"))
      (node (ref "LED42") (pin "4") (pinfunction "C_4") (pintype "passive"))
    )
    (net (code "42") (name "Net-(LED37-D)") (class "Default")
      (node (ref "LED37") (pin "2") (pinfunction "D_2") (pintype "passive"))
      (node (ref "LED38") (pin "2") (pinfunction "D_2") (pintype "passive"))
      (node (ref "LED39") (pin "2") (pinfunction "D_2") (pintype "passive"))
      (node (ref "LED40") (pin "2") (pinfunction "D_2") (pintype "passive"))
      (node (ref "LED41") (pin "2") (pinfunction "D_2") (pintype "passive"))
      (node (ref "LED42") (pin "2") (pinfunction "D_2") (pintype "passive"))
    )
    (net (code "43") (name "Net-(LED37-DP)") (class "Default")
      (node (ref "LED37") (pin "5") (pinfunction "DP_5") (pintype "passive"))
      (node (ref "LED38") (pin "5") (pinfunction "DP_5") (pintype "passive"))
      (node (ref "LED39") (pin "5") (pinfunction "DP_5") (pintype "passive"))
      (node (ref "LED40") (pin "5") (pinfunction "DP_5") (pintype "passive"))
      (node (ref "LED41") (pin "5") (pinfunction "DP_5") (pintype "passive"))
      (node (ref "LED42") (pin "5") (pinfunction "DP_5") (pintype "passive"))
    )
    (net (code "44") (name "Net-(LED37-E)") (class "Default")
      (node (ref "LED37") (pin "1") (pinfunction "E_1") (pintype "passive"))
      (node (ref "LED38") (pin "1") (pinfunction "E_1") (pintype "passive"))
      (node (ref "LED39") (pin "1") (pinfunction "E_1") (pintype "passive"))
      (node (ref "LED40") (pin "1") (pinfunction "E_1") (pintype "passive"))
      (node (ref "LED41") (pin "1") (pinfunction "E_1") (pintype "passive"))
      (node (ref "LED42") (pin "1") (pinfunction "E_1") (pintype "passive"))
    )
    (net (code "45") (name "Net-(LED37-F)") (class "Default")
      (node (ref "LED37") (pin "9") (pinfunction "F_9") (pintype "passive"))
      (node (ref "LED38") (pin "9") (pinfunction "F_9") (pintype "passive"))
      (node (ref "LED39") (pin "9") (pinfunction "F_9") (pintype "passive"))
      (node (ref "LED40") (pin "9") (pinfunction "F_9") (pintype "passive"))
      (node (ref "LED41") (pin "9") (pinfunction "F_9") (pintype "passive"))
      (node (ref "LED42") (pin "9") (pinfunction "F_9") (pintype "passive"))
    )
    (net (code "46") (name "Net-(LED37-G)") (class "Default")
      (node (ref "LED37") (pin "10") (pinfunction "G_10") (pintype "passive"))
      (node (ref "LED38") (pin "10") (pinfunction "G_10") (pintype "passive"))
      (node (ref "LED39") (pin "10") (pinfunction "G_10") (pintype "passive"))
      (node (ref "LED40") (pin "10") (pinfunction "G_10") (pintype "passive"))
      (node (ref "LED41") (pin "10") (pinfunction "G_10") (pintype "passive"))
      (node (ref "LED42") (pin "10") (pinfunction "G_10") (pintype "passive"))
    )
    (net (code "47") (name "Net-(LED43-A)") (class "Default")
      (node (ref "LED43") (pin "7") (pinfunction "A_7") (pintype "passive"))
      (node (ref "LED44") (pin "7") (pinfunction "A_7") (pintype "passive"))
      (node (ref "LED45") (pin "7") (pinfunction "A_7") (pintype "passive"))
      (node (ref "LED46") (pin "7") (pinfunction "A_7") (pintype "passive"))
      (node (ref "LED47") (pin "7") (pinfunction "A_7") (pintype "passive"))
      (node (ref "LED48") (pin "7") (pinfunction "A_7") (pintype "passive"))
    )
    (net (code "48") (name "Net-(LED43-B)") (class "Default")
      (node (ref "LED43") (pin "6") (pinfunction "B_6") (pintype "passive"))
      (node (ref "LED44") (pin "6") (pinfunction "B_6") (pintype "passive"))
      (node (ref "LED45") (pin "6") (pinfunction "B_6") (pintype "passive"))
      (node (ref "LED46") (pin "6") (pinfunction "B_6") (pintype "passive"))
      (node (ref "LED47") (pin "6") (pinfunction "B_6") (pintype "passive"))
      (node (ref "LED48") (pin "6") (pinfunction "B_6") (pintype "passive"))
    )
    (net (code "49") (name "Net-(LED43-C)") (class "Default")
      (node (ref "LED43") (pin "4") (pinfunction "C_4") (pintype "passive"))
      (node (ref "LED44") (pin "4") (pinfunction "C_4") (pintype "passive"))
      (node (ref "LED45") (pin "4") (pinfunction "C_4") (pintype "passive"))
      (node (ref "LED46") (pin "4") (pinfunction "C_4") (pintype "passive"))
      (node (ref "LED47") (pin "4") (pinfunction "C_4") (pintype "passive"))
      (node (ref "LED48") (pin "4") (pinfunction "C_4") (pintype "passive"))
    )
    (net (code "50") (name "Net-(LED43-D)") (class "Default")
      (node (ref "LED43") (pin "2") (pinfunction "D_2") (pintype "passive"))
      (node (ref "LED44") (pin "2") (pinfunction "D_2") (pintype "passive"))
      (node (ref "LED45") (pin "2") (pinfunction "D_2") (pintype "passive"))
      (node (ref "LED46") (pin "2") (pinfunction "D_2") (pintype "passive"))
      (node (ref "LED47") (pin "2") (pinfunction "D_2") (pintype "passive"))
      (node (ref "LED48") (pin "2") (pinfunction "D_2") (pintype "passive"))
    )
    (net (code "51") (name "Net-(LED43-DP)") (class "Default")
      (node (ref "LED43") (pin "5") (pinfunction "DP_5") (pintype "passive"))
      (node (ref "LED44") (pin "5") (pinfunction "DP_5") (pintype "passive"))
      (node (ref "LED45") (pin "5") (pinfunction "DP_5") (pintype "passive"))
      (node (ref "LED46") (pin "5") (pinfunction "DP_5") (pintype "passive"))
      (node (ref "LED47") (pin "5") (pinfunction "DP_5") (pintype "passive"))
      (node (ref "LED48") (pin "5") (pinfunction "DP_5") (pintype "passive"))
    )
    (net (code "52") (name "Net-(LED43-E)") (class "Default")
      (node (ref "LED43") (pin "1") (pinfunction "E_1") (pintype "passive"))
      (node (ref "LED44") (pin "1") (pinfunction "E_1") (pintype "passive"))
      (node (ref "LED45") (pin "1") (pinfunction "E_1") (pintype "passive"))
      (node (ref "LED46") (pin "1") (pinfunction "E_1") (pintype "passive"))
      (node (ref "LED47") (pin "1") (pinfunction "E_1") (pintype "passive"))
      (node (ref "LED48") (pin "1") (pinfunction "E_1") (pintype "passive"))
    )
    (net (code "53") (name "Net-(LED43-F)") (class "Default")
      (node (ref "LED43") (pin "9") (pinfunction "F_9") (pintype "passive"))
      (node (ref "LED44") (pin "9") (pinfunction "F_9") (pintype "passive"))
      (node (ref "LED45") (pin "9") (pinfunction "F_9") (pintype "passive"))
      (node (ref "LED46") (pin "9") (pinfunction "F_9") (pintype "passive"))
      (node (ref "LED47") (pin "9") (pinfunction "F_9") (pintype "passive"))
      (node (ref "LED48") (pin "9") (pinfunction "F_9") (pintype "passive"))
    )
    (net (code "54") (name "Net-(LED43-G)") (class "Default")
      (node (ref "LED43") (pin "10") (pinfunction "G_10") (pintype "passive"))
      (node (ref "LED44") (pin "10") (pinfunction "G_10") (pintype "passive"))
      (node (ref "LED45") (pin "10") (pinfunction "G_10") (pintype "passive"))
      (node (ref "LED46") (pin "10") (pinfunction "G_10") (pintype "passive"))
      (node (ref "LED47") (pin "10") (pinfunction "G_10") (pintype "passive"))
      (node (ref "LED48") (pin "10") (pinfunction "G_10") (pintype "passive"))
    )
    (net (code "55") (name "Net-(LED61-A)") (class "Default")
      (node (ref "LED61") (pin "7") (pinfunction "A_7") (pintype "passive"))
      (node (ref "LED62") (pin "7") (pinfunction "A_7") (pintype "passive"))
      (node (ref "LED63") (pin "7") (pinfunction "A_7") (pintype "passive"))
      (node (ref "LED64") (pin "7") (pinfunction "A_7") (pintype "passive"))
      (node (ref "LED65") (pin "7") (pinfunction "A_7") (pintype "passive"))
      (node (ref "LED66") (pin "7") (pinfunction "A_7") (pintype "passive"))
    )
    (net (code "56") (name "Net-(LED61-B)") (class "Default")
      (node (ref "LED61") (pin "6") (pinfunction "B_6") (pintype "passive"))
      (node (ref "LED62") (pin "6") (pinfunction "B_6") (pintype "passive"))
      (node (ref "LED63") (pin "6") (pinfunction "B_6") (pintype "passive"))
      (node (ref "LED64") (pin "6") (pinfunction "B_6") (pintype "passive"))
      (node (ref "LED65") (pin "6") (pinfunction "B_6") (pintype "passive"))
      (node (ref "LED66") (pin "6") (pinfunction "B_6") (pintype "passive"))
    )
    (net (code "57") (name "Net-(LED61-C)") (class "Default")
      (node (ref "LED61") (pin "4") (pinfunction "C_4") (pintype "passive"))
      (node (ref "LED62") (pin "4") (pinfunction "C_4") (pintype "passive"))
      (node (ref "LED63") (pin "4") (pinfunction "C_4") (pintype "passive"))
      (node (ref "LED64") (pin "4") (pinfunction "C_4") (pintype "passive"))
      (node (ref "LED65") (pin "4") (pinfunction "C_4") (pintype "passive"))
      (node (ref "LED66") (pin "4") (pinfunction "C_4") (pintype "passive"))
    )
    (net (code "58") (name "Net-(LED61-D)") (class "Default")
      (node (ref "LED61") (pin "2") (pinfunction "D_2") (pintype "passive"))
      (node (ref "LED62") (pin "2") (pinfunction "D_2") (pintype "passive"))
      (node (ref "LED63") (pin "2") (pinfunction "D_2") (pintype "passive"))
      (node (ref "LED64") (pin "2") (pinfunction "D_2") (pintype "passive"))
      (node (ref "LED65") (pin "2") (pinfunction "D_2") (pintype "passive"))
      (node (ref "LED66") (pin "2") (pinfunction "D_2") (pintype "passive"))
    )
    (net (code "59") (name "Net-(LED61-DP)") (class "Default")
      (node (ref "LED61") (pin "5") (pinfunction "DP_5") (pintype "passive"))
      (node (ref "LED62") (pin "5") (pinfunction "DP_5") (pintype "passive"))
      (node (ref "LED63") (pin "5") (pinfunction "DP_5") (pintype "passive"))
      (node (ref "LED64") (pin "5") (pinfunction "DP_5") (pintype "passive"))
      (node (ref "LED65") (pin "5") (pinfunction "DP_5") (pintype "passive"))
      (node (ref "LED66") (pin "5") (pinfunction "DP_5") (pintype "passive"))
    )
    (net (code "60") (name "Net-(LED61-E)") (class "Default")
      (node (ref "LED61") (pin "1") (pinfunction "E_1") (pintype "passive"))
      (node (ref "LED62") (pin "1") (pinfunction "E_1") (pintype "passive"))
      (node (ref "LED63") (pin "1") (pinfunction "E_1") (pintype "passive"))
      (node (ref "LED64") (pin "1") (pinfunction "E_1") (pintype "passive"))
      (node (ref "LED65") (pin "1") (pinfunction "E_1") (pintype "passive"))
      (node (ref "LED66") (pin "1") (pinfunction "E_1") (pintype "passive"))
    )
    (net (code "61") (name "Net-(LED61-F)") (class "Default")
      (node (ref "LED61") (pin "9") (pinfunction "F_9") (pintype "passive"))
      (node (ref "LED62") (pin "9") (pinfunction "F_9") (pintype "passive"))
      (node (ref "LED63") (pin "9") (pinfunction "F_9") (pintype "passive"))
      (node (ref "LED64") (pin "9") (pinfunction "F_9") (pintype "passive"))
      (node (ref "LED65") (pin "9") (pinfunction "F_9") (pintype "passive"))
      (node (ref "LED66") (pin "9") (pinfunction "F_9") (pintype "passive"))
    )
    (net (code "62") (name "Net-(LED61-G)") (class "Default")
      (node (ref "LED61") (pin "10") (pinfunction "G_10") (pintype "passive"))
      (node (ref "LED62") (pin "10") (pinfunction "G_10") (pintype "passive"))
      (node (ref "LED63") (pin "10") (pinfunction "G_10") (pintype "passive"))
      (node (ref "LED64") (pin "10") (pinfunction "G_10") (pintype "passive"))
      (node (ref "LED65") (pin "10") (pinfunction "G_10") (pintype "passive"))
      (node (ref "LED66") (pin "10") (pinfunction "G_10") (pintype "passive"))
    )
    (net (code "63") (name "Net-(LED67-A)") (class "Default")
      (node (ref "LED67") (pin "7") (pinfunction "A_7") (pintype "passive"))
      (node (ref "LED68") (pin "7") (pinfunction "A_7") (pintype "passive"))
      (node (ref "LED69") (pin "7") (pinfunction "A_7") (pintype "passive"))
      (node (ref "LED70") (pin "7") (pinfunction "A_7") (pintype "passive"))
      (node (ref "LED71") (pin "7") (pinfunction "A_7") (pintype "passive"))
      (node (ref "LED72") (pin "7") (pinfunction "A_7") (pintype "passive"))
    )
    (net (code "64") (name "Net-(LED67-B)") (class "Default")
      (node (ref "LED67") (pin "6") (pinfunction "B_6") (pintype "passive"))
      (node (ref "LED68") (pin "6") (pinfunction "B_6") (pintype "passive"))
      (node (ref "LED69") (pin "6") (pinfunction "B_6") (pintype "passive"))
      (node (ref "LED70") (pin "6") (pinfunction "B_6") (pintype "passive"))
      (node (ref "LED71") (pin "6") (pinfunction "B_6") (pintype "passive"))
      (node (ref "LED72") (pin "6") (pinfunction "B_6") (pintype "passive"))
    )
    (net (code "65") (name "Net-(LED67-C)") (class "Default")
      (node (ref "LED67") (pin "4") (pinfunction "C_4") (pintype "passive"))
      (node (ref "LED68") (pin "4") (pinfunction "C_4") (pintype "passive"))
      (node (ref "LED69") (pin "4") (pinfunction "C_4") (pintype "passive"))
      (node (ref "LED70") (pin "4") (pinfunction "C_4") (pintype "passive"))
      (node (ref "LED71") (pin "4") (pinfunction "C_4") (pintype "passive"))
      (node (ref "LED72") (pin "4") (pinfunction "C_4") (pintype "passive"))
    )
    (net (code "66") (name "Net-(LED67-D)") (class "Default")
      (node (ref "LED67") (pin "2") (pinfunction "D_2") (pintype "passive"))
      (node (ref "LED68") (pin "2") (pinfunction "D_2") (pintype "passive"))
      (node (ref "LED69") (pin "2") (pinfunction "D_2") (pintype "passive"))
      (node (ref "LED70") (pin "2") (pinfunction "D_2") (pintype "passive"))
      (node (ref "LED71") (pin "2") (pinfunction "D_2") (pintype "passive"))
      (node (ref "LED72") (pin "2") (pinfunction "D_2") (pintype "passive"))
    )
    (net (code "67") (name "Net-(LED67-DP)") (class "Default")
      (node (ref "LED67") (pin "5") (pinfunction "DP_5") (pintype "passive"))
      (node (ref "LED68") (pin "5") (pinfunction "DP_5") (pintype "passive"))
      (node (ref "LED69") (pin "5") (pinfunction "DP_5") (pintype "passive"))
      (node (ref "LED70") (pin "5") (pinfunction "DP_5") (pintype "passive"))
      (node (ref "LED71") (pin "5") (pinfunction "DP_5") (pintype "passive"))
      (node (ref "LED72") (pin "5") (pinfunction "DP_5") (pintype "passive"))
    )
    (net (code "68") (name "Net-(LED67-E)") (class "Default")
      (node (ref "LED67") (pin "1") (pinfunction "E_1") (pintype "passive"))
      (node (ref "LED68") (pin "1") (pinfunction "E_1") (pintype "passive"))
      (node (ref "LED69") (pin "1") (pinfunction "E_1") (pintype "passive"))
      (node (ref "LED70") (pin "1") (pinfunction "E_1") (pintype "passive"))
      (node (ref "LED71") (pin "1") (pinfunction "E_1") (pintype "passive"))
      (node (ref "LED72") (pin "1") (pinfunction "E_1") (pintype "passive"))
    )
    (net (code "69") (name "Net-(LED67-F)") (class "Default")
      (node (ref "LED67") (pin "9") (pinfunction "F_9") (pintype "passive"))
      (node (ref "LED68") (pin "9") (pinfunction "F_9") (pintype "passive"))
      (node (ref "LED69") (pin "9") (pinfunction "F_9") (pintype "passive"))
      (node (ref "LED70") (pin "9") (pinfunction "F_9") (pintype "passive"))
      (node (ref "LED71") (pin "9") (pinfunction "F_9") (pintype "passive"))
      (node (ref "LED72") (pin "9") (pinfunction "F_9") (pintype "passive"))
    )
    (net (code "70") (name "Net-(LED67-G)") (class "Default")
      (node (ref "LED67") (pin "10") (pinfunction "G_10") (pintype "passive"))
      (node (ref "LED68") (pin "10") (pinfunction "G_10") (pintype "passive"))
      (node (ref "LED69") (pin "10") (pinfunction "G_10") (pintype "passive"))
      (node (ref "LED70") (pin "10") (pinfunction "G_10") (pintype "passive"))
      (node (ref "LED71") (pin "10") (pinfunction "G_10") (pintype "passive"))
      (node (ref "LED72") (pin "10") (pinfunction "G_10") (pintype "passive"))
    )
  )
)
